# bridgeScheme.net
KiCad netlist of a schematic drawn in EAGLE
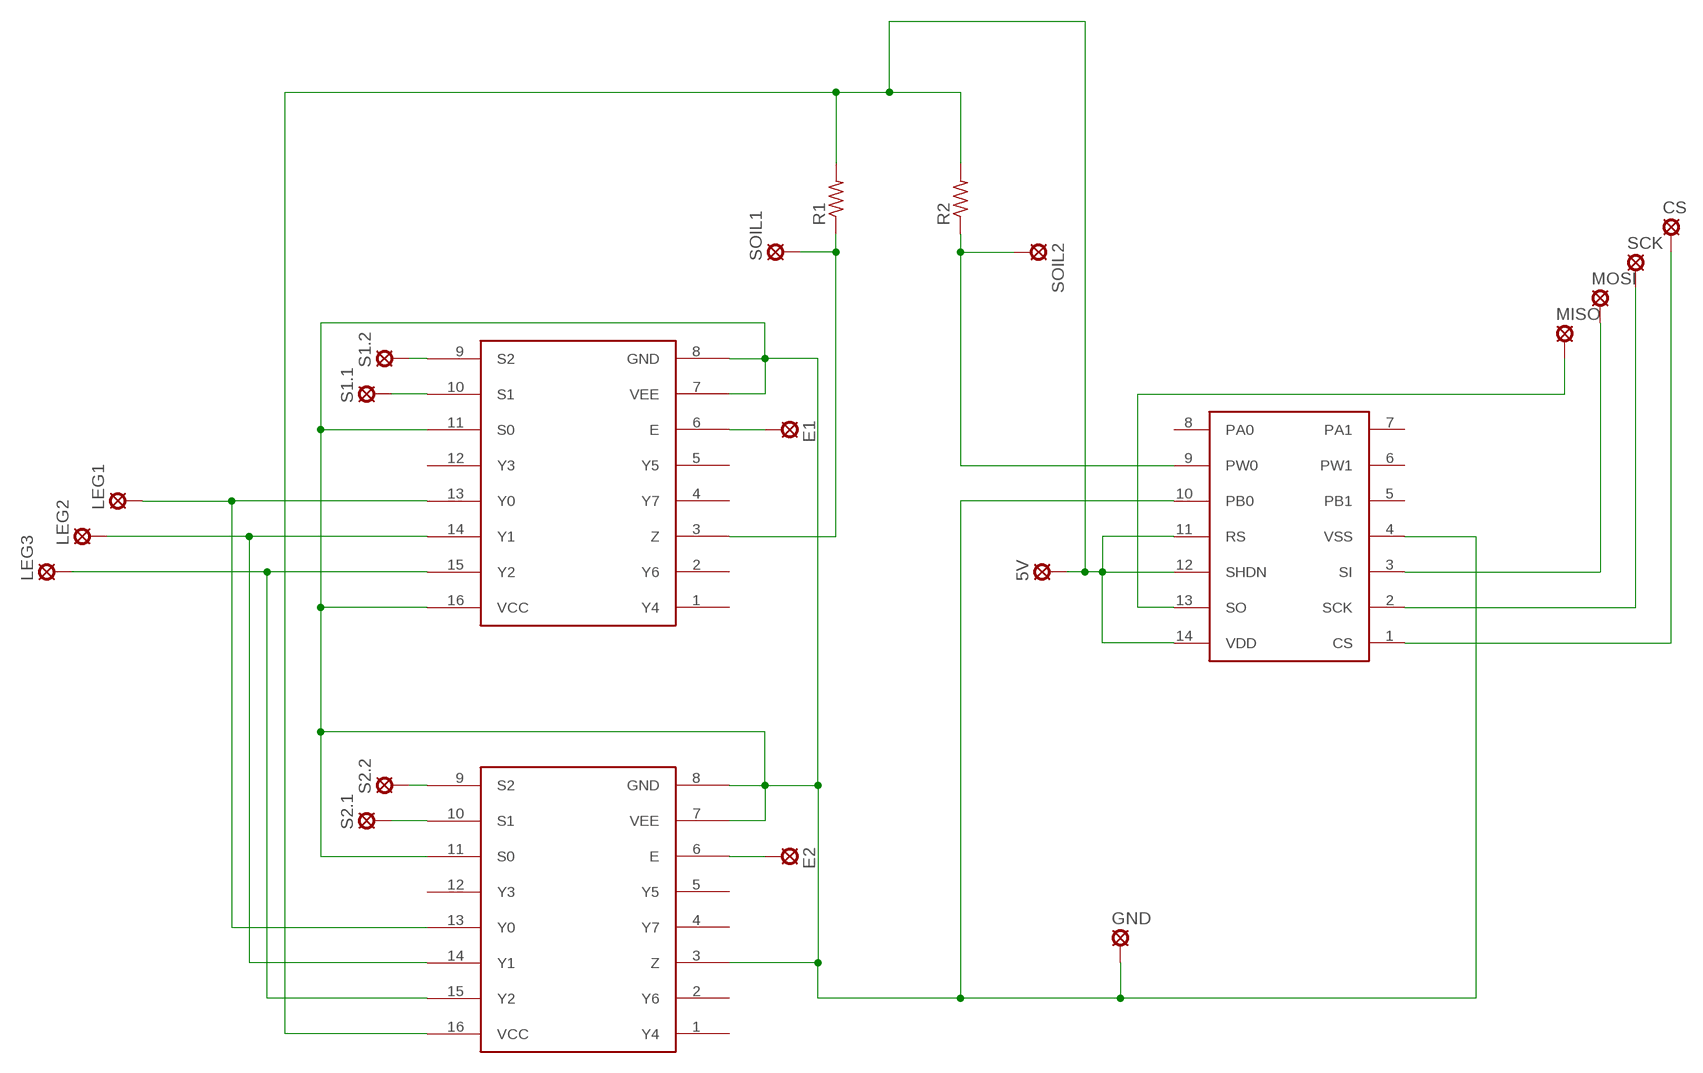
[diagram p0: schematic, sheet 1]

(export (version "E")
  (design (tool "Eeschema 10.0.6"))
  (components
    (comp (ref "5V")
      (value "LSP10")
      (footprint "eagle-import:LSP10")
      (libsource (lib "eagle-import") (part "LSP10"))
    )
    (comp (ref "CS")
      (value "LSP10")
      (footprint "eagle-import:LSP10")
      (libsource (lib "eagle-import") (part "LSP10"))
    )
    (comp (ref "E1")
      (value "LSP10")
      (footprint "eagle-import:LSP10")
      (libsource (lib "eagle-import") (part "LSP10"))
    )
    (comp (ref "E2")
      (value "LSP10")
      (footprint "eagle-import:LSP10")
      (libsource (lib "eagle-import") (part "LSP10"))
    )
    (comp (ref "GND")
      (value "LSP10")
      (footprint "eagle-import:LSP10")
      (libsource (lib "eagle-import") (part "LSP10"))
    )
    (comp (ref "LEG1")
      (value "LSP10")
      (footprint "eagle-import:LSP10")
      (libsource (lib "eagle-import") (part "LSP10"))
    )
    (comp (ref "LEG2")
      (value "LSP10")
      (footprint "eagle-import:LSP10")
      (libsource (lib "eagle-import") (part "LSP10"))
    )
    (comp (ref "LEG3")
      (value "LSP10")
      (footprint "eagle-import:LSP10")
      (libsource (lib "eagle-import") (part "LSP10"))
    )
    (comp (ref "MISO")
      (value "LSP10")
      (footprint "eagle-import:LSP10")
      (libsource (lib "eagle-import") (part "LSP10"))
    )
    (comp (ref "MOSI")
      (value "LSP10")
      (footprint "eagle-import:LSP10")
      (libsource (lib "eagle-import") (part "LSP10"))
    )
    (comp (ref "R1")
      (value "R-US_0207/10")
      (footprint "eagle-import:0207_10")
      (libsource (lib "eagle-import") (part "R-US_0207/10"))
    )
    (comp (ref "R2")
      (value "R-US_0207/10")
      (footprint "eagle-import:0207_10")
      (libsource (lib "eagle-import") (part "R-US_0207/10"))
    )
    (comp (ref "S1.1")
      (value "LSP10")
      (footprint "eagle-import:LSP10")
      (libsource (lib "eagle-import") (part "LSP10"))
    )
    (comp (ref "S1.2")
      (value "LSP10")
      (footprint "eagle-import:LSP10")
      (libsource (lib "eagle-import") (part "LSP10"))
    )
    (comp (ref "S2.1")
      (value "LSP10")
      (footprint "eagle-import:LSP10")
      (libsource (lib "eagle-import") (part "LSP10"))
    )
    (comp (ref "S2.2")
      (value "LSP10")
      (footprint "eagle-import:LSP10")
      (libsource (lib "eagle-import") (part "LSP10"))
    )
    (comp (ref "SCK")
      (value "LSP10")
      (footprint "eagle-import:LSP10")
      (libsource (lib "eagle-import") (part "LSP10"))
    )
    (comp (ref "SOIL1")
      (value "LSP10")
      (footprint "eagle-import:LSP10")
      (libsource (lib "eagle-import") (part "LSP10"))
    )
    (comp (ref "SOIL2")
      (value "LSP10")
      (footprint "eagle-import:LSP10")
      (libsource (lib "eagle-import") (part "LSP10"))
    )
    (comp (ref "U$1")
      (value "MCP42100!")
      (footprint "eagle-import:DIL14")
      (libsource (lib "eagle-import") (part "MCP42100!"))
    )
    (comp (ref "U$2")
      (value "74HC4051!")
      (footprint "eagle-import:DIL16")
      (libsource (lib "eagle-import") (part "74HC4051!"))
    )
    (comp (ref "U$3")
      (value "74HC4051!")
      (footprint "eagle-import:DIL16")
      (libsource (lib "eagle-import") (part "74HC4051!"))
    )
  )
  (nets
    (net (code "1") (name "Net-(U$1-CS)") (class "Default")
      (node (ref "CS") (pin "MP") (pinfunction "MP_MP") (pintype "passive"))
      (node (ref "U$1") (pin "1") (pinfunction "CS_1") (pintype "bidirectional"))
    )
    (net (code "2") (name "Net-(U$1-PB0)") (class "Default")
      (node (ref "GND") (pin "MP") (pinfunction "MP_MP") (pintype "passive"))
      (node (ref "U$1") (pin "10") (pinfunction "PB0_10") (pintype "bidirectional"))
      (node (ref "U$1") (pin "4") (pinfunction "VSS_4") (pintype "bidirectional"))
      (node (ref "U$2") (pin "11") (pinfunction "S0_11") (pintype "bidirectional"))
      (node (ref "U$2") (pin "16") (pinfunction "VCC_16") (pintype "bidirectional"))
      (node (ref "U$2") (pin "7") (pinfunction "VEE_7") (pintype "bidirectional"))
      (node (ref "U$2") (pin "8") (pinfunction "GND_8") (pintype "bidirectional"))
      (node (ref "U$3") (pin "11") (pinfunction "S0_11") (pintype "bidirectional"))
      (node (ref "U$3") (pin "3") (pinfunction "Z_3") (pintype "bidirectional"))
      (node (ref "U$3") (pin "7") (pinfunction "VEE_7") (pintype "bidirectional"))
      (node (ref "U$3") (pin "8") (pinfunction "GND_8") (pintype "bidirectional"))
    )
    (net (code "3") (name "Net-(U$1-PW0)") (class "Default")
      (node (ref "R2") (pin "1") (pinfunction "1_1") (pintype "passive"))
      (node (ref "SOIL2") (pin "MP") (pinfunction "MP_MP") (pintype "passive"))
      (node (ref "U$1") (pin "9") (pinfunction "PW0_9") (pintype "bidirectional"))
    )
    (net (code "4") (name "Net-(U$1-RS)") (class "Default")
      (node (ref "5V") (pin "MP") (pinfunction "MP_MP") (pintype "passive"))
      (node (ref "R1") (pin "2") (pinfunction "2_2") (pintype "passive"))
      (node (ref "R2") (pin "2") (pinfunction "2_2") (pintype "passive"))
      (node (ref "U$1") (pin "11") (pinfunction "RS_11") (pintype "bidirectional"))
      (node (ref "U$1") (pin "12") (pinfunction "SHDN_12") (pintype "bidirectional"))
      (node (ref "U$1") (pin "14") (pinfunction "VDD_14") (pintype "bidirectional"))
      (node (ref "U$3") (pin "16") (pinfunction "VCC_16") (pintype "bidirectional"))
    )
    (net (code "5") (name "Net-(U$1-SCK)") (class "Default")
      (node (ref "SCK") (pin "MP") (pinfunction "MP_MP") (pintype "passive"))
      (node (ref "U$1") (pin "2") (pinfunction "SCK_2") (pintype "bidirectional"))
    )
    (net (code "6") (name "Net-(U$1-SI)") (class "Default")
      (node (ref "MOSI") (pin "MP") (pinfunction "MP_MP") (pintype "passive"))
      (node (ref "U$1") (pin "3") (pinfunction "SI_3") (pintype "bidirectional"))
    )
    (net (code "7") (name "Net-(U$1-SO)") (class "Default")
      (node (ref "MISO") (pin "MP") (pinfunction "MP_MP") (pintype "passive"))
      (node (ref "U$1") (pin "13") (pinfunction "SO_13") (pintype "bidirectional"))
    )
    (net (code "8") (name "Net-(U$2-E)") (class "Default")
      (node (ref "E1") (pin "MP") (pinfunction "MP_MP") (pintype "passive"))
      (node (ref "U$2") (pin "6") (pinfunction "E_6") (pintype "bidirectional"))
    )
    (net (code "9") (name "Net-(U$2-S1)") (class "Default")
      (node (ref "S1.1") (pin "MP") (pinfunction "MP_MP") (pintype "passive"))
      (node (ref "U$2") (pin "10") (pinfunction "S1_10") (pintype "bidirectional"))
    )
    (net (code "10") (name "Net-(U$2-S2)") (class "Default")
      (node (ref "S1.2") (pin "MP") (pinfunction "MP_MP") (pintype "passive"))
      (node (ref "U$2") (pin "9") (pinfunction "S2_9") (pintype "bidirectional"))
    )
    (net (code "11") (name "Net-(U$2-Y0)") (class "Default")
      (node (ref "LEG1") (pin "MP") (pinfunction "MP_MP") (pintype "passive"))
      (node (ref "U$2") (pin "13") (pinfunction "Y0_13") (pintype "bidirectional"))
      (node (ref "U$3") (pin "13") (pinfunction "Y0_13") (pintype "bidirectional"))
    )
    (net (code "12") (name "Net-(U$2-Y1)") (class "Default")
      (node (ref "LEG2") (pin "MP") (pinfunction "MP_MP") (pintype "passive"))
      (node (ref "U$2") (pin "14") (pinfunction "Y1_14") (pintype "bidirectional"))
      (node (ref "U$3") (pin "14") (pinfunction "Y1_14") (pintype "bidirectional"))
    )
    (net (code "13") (name "Net-(U$2-Y2)") (class "Default")
      (node (ref "LEG3") (pin "MP") (pinfunction "MP_MP") (pintype "passive"))
      (node (ref "U$2") (pin "15") (pinfunction "Y2_15") (pintype "bidirectional"))
      (node (ref "U$3") (pin "15") (pinfunction "Y2_15") (pintype "bidirectional"))
    )
    (net (code "14") (name "Net-(U$2-Z)") (class "Default")
      (node (ref "R1") (pin "1") (pinfunction "1_1") (pintype "passive"))
      (node (ref "SOIL1") (pin "MP") (pinfunction "MP_MP") (pintype "passive"))
      (node (ref "U$2") (pin "3") (pinfunction "Z_3") (pintype "bidirectional"))
    )
    (net (code "15") (name "Net-(U$3-E)") (class "Default")
      (node (ref "E2") (pin "MP") (pinfunction "MP_MP") (pintype "passive"))
      (node (ref "U$3") (pin "6") (pinfunction "E_6") (pintype "bidirectional"))
    )
    (net (code "16") (name "Net-(U$3-S1)") (class "Default")
      (node (ref "S2.1") (pin "MP") (pinfunction "MP_MP") (pintype "passive"))
      (node (ref "U$3") (pin "10") (pinfunction "S1_10") (pintype "bidirectional"))
    )
    (net (code "17") (name "Net-(U$3-S2)") (class "Default")
      (node (ref "S2.2") (pin "MP") (pinfunction "MP_MP") (pintype "passive"))
      (node (ref "U$3") (pin "9") (pinfunction "S2_9") (pintype "bidirectional"))
    )
    (net (code "18") (name "unconnected-(U$1-PA0-Pad8)") (class "Default")
      (node (ref "U$1") (pin "8") (pinfunction "PA0_8") (pintype "bidirectional"))
    )
    (net (code "19") (name "unconnected-(U$1-PA1-Pad7)") (class "Default")
      (node (ref "U$1") (pin "7") (pinfunction "PA1_7") (pintype "bidirectional"))
    )
    (net (code "20") (name "unconnected-(U$1-PB1-Pad5)") (class "Default")
      (node (ref "U$1") (pin "5") (pinfunction "PB1_5") (pintype "bidirectional"))
    )
    (net (code "21") (name "unconnected-(U$1-PW1-Pad6)") (class "Default")
      (node (ref "U$1") (pin "6") (pinfunction "PW1_6") (pintype "bidirectional"))
    )
    (net (code "22") (name "unconnected-(U$2-Y3-Pad12)") (class "Default")
      (node (ref "U$2") (pin "12") (pinfunction "Y3_12") (pintype "bidirectional"))
    )
    (net (code "23") (name "unconnected-(U$2-Y4-Pad1)") (class "Default")
      (node (ref "U$2") (pin "1") (pinfunction "Y4_1") (pintype "bidirectional"))
    )
    (net (code "24") (name "unconnected-(U$2-Y5-Pad5)") (class "Default")
      (node (ref "U$2") (pin "5") (pinfunction "Y5_5") (pintype "bidirectional"))
    )
    (net (code "25") (name "unconnected-(U$2-Y6-Pad2)") (class "Default")
      (node (ref "U$2") (pin "2") (pinfunction "Y6_2") (pintype "bidirectional"))
    )
    (net (code "26") (name "unconnected-(U$2-Y7-Pad4)") (class "Default")
      (node (ref "U$2") (pin "4") (pinfunction "Y7_4") (pintype "bidirectional"))
    )
    (net (code "27") (name "unconnected-(U$3-Y3-Pad12)") (class "Default")
      (node (ref "U$3") (pin "12") (pinfunction "Y3_12") (pintype "bidirectional"))
    )
    (net (code "28") (name "unconnected-(U$3-Y4-Pad1)") (class "Default")
      (node (ref "U$3") (pin "1") (pinfunction "Y4_1") (pintype "bidirectional"))
    )
    (net (code "29") (name "unconnected-(U$3-Y5-Pad5)") (class "Default")
      (node (ref "U$3") (pin "5") (pinfunction "Y5_5") (pintype "bidirectional"))
    )
    (net (code "30") (name "unconnected-(U$3-Y6-Pad2)") (class "Default")
      (node (ref "U$3") (pin "2") (pinfunction "Y6_2") (pintype "bidirectional"))
    )
    (net (code "31") (name "unconnected-(U$3-Y7-Pad4)") (class "Default")
      (node (ref "U$3") (pin "4") (pinfunction "Y7_4") (pintype "bidirectional"))
    )
  )
)
